# bord_EAGLE_projet_elec_sans_resistance.net
KiCad netlist of a schematic drawn in EAGLE
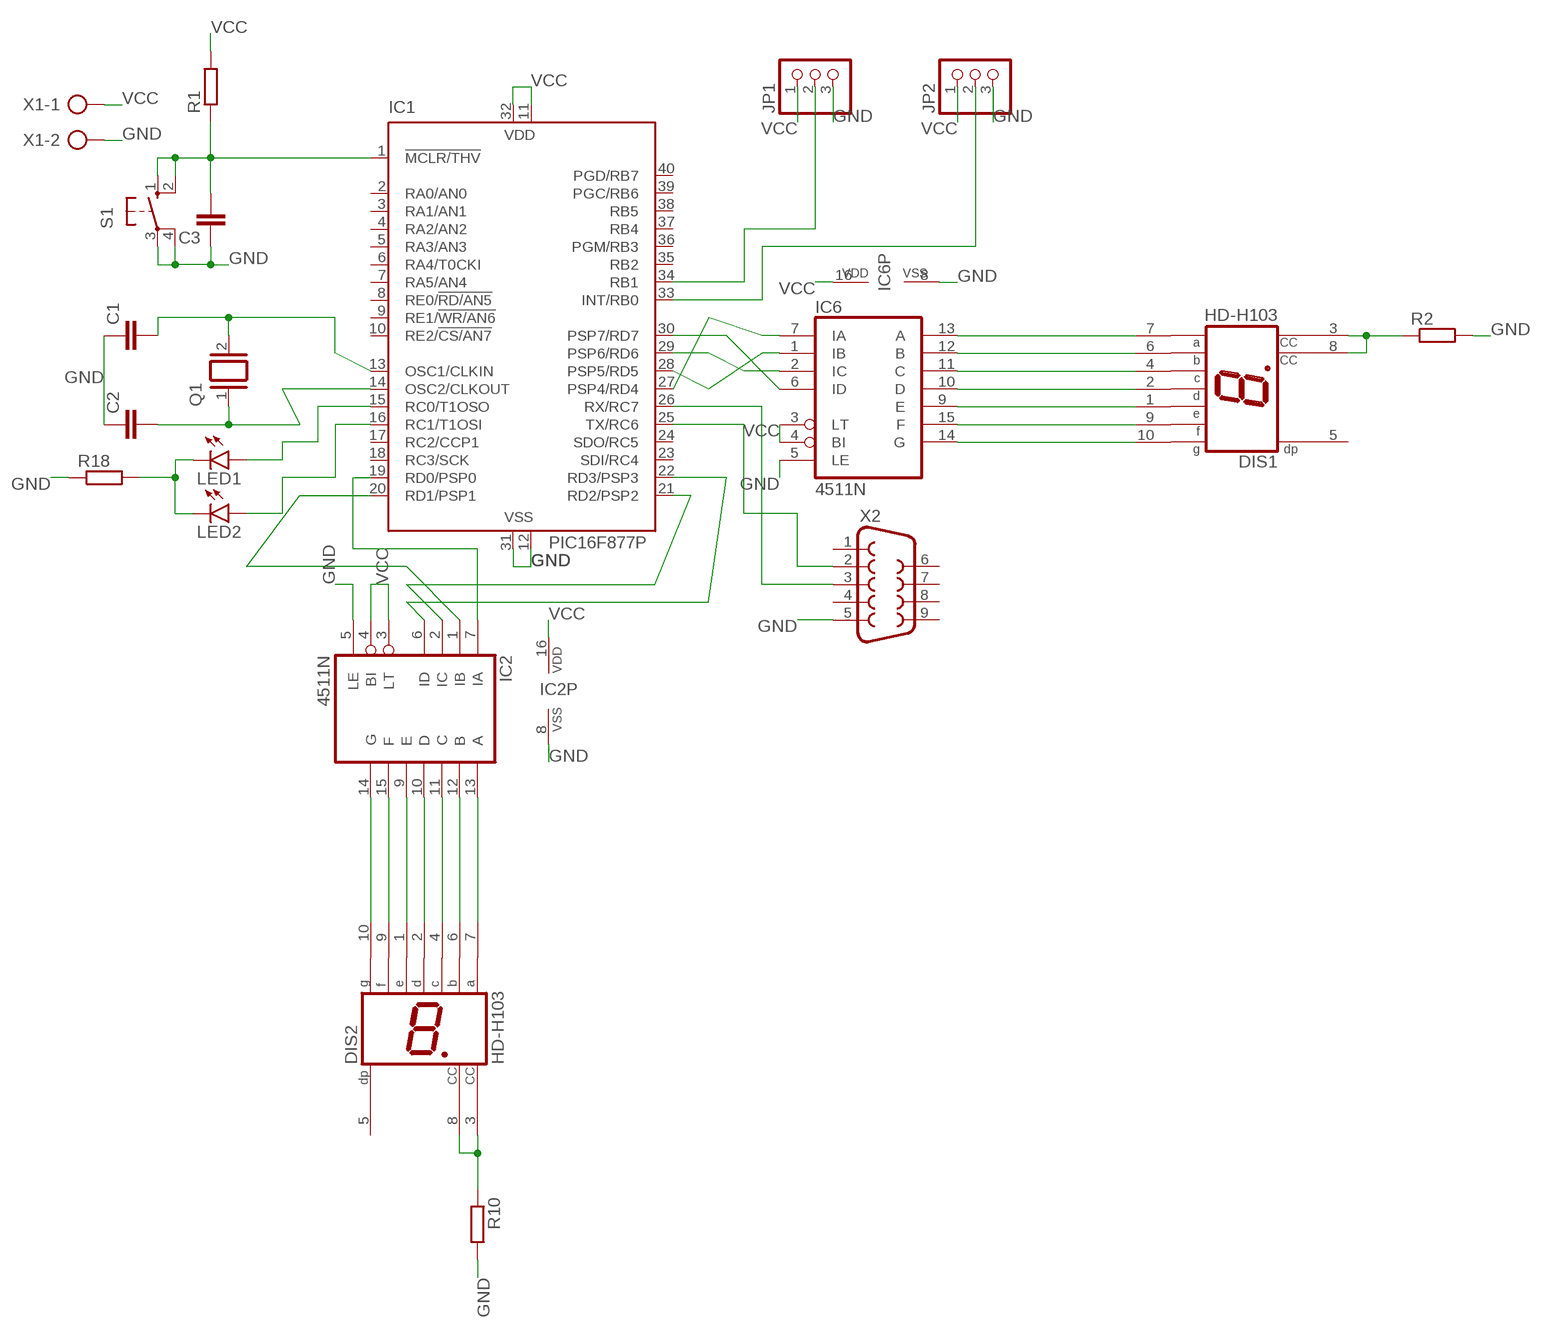
[diagram p0: schematic, sheet 1]

(export (version "E")
  (design (tool "Eeschema 10.0.6"))
  (components
    (comp (ref "C1")
      (value "C-EU025-025X050")
      (footprint "eagle-import:C025-025X050")
      (libsource (lib "eagle-import") (part "C-EU025-025X050"))
    )
    (comp (ref "C2")
      (value "C-EU025-025X050")
      (footprint "eagle-import:C025-025X050")
      (libsource (lib "eagle-import") (part "C-EU025-025X050"))
    )
    (comp (ref "C3")
      (value "C-EU025-024X044")
      (footprint "eagle-import:C025-024X044")
      (libsource (lib "eagle-import") (part "C-EU025-024X044"))
    )
    (comp (ref "DIS1")
      (value "HD-H103")
      (footprint "eagle-import:HDSP-M")
      (libsource (lib "eagle-import") (part "HD-H103"))
    )
    (comp (ref "DIS2")
      (value "HD-H103")
      (footprint "eagle-import:HDSP-M")
      (libsource (lib "eagle-import") (part "HD-H103"))
    )
    (comp (ref "IC1")
      (value "PIC16F877P")
      (footprint "eagle-import:DIL40")
      (fields (field (name "MF") "MICROCHIP") (field (name "MPN") "PIC16F877-04/P"))
      (libsource (lib "eagle-import") (part "PIC16F87P7"))
    )
    (comp (ref "IC2")
      (value "4511N")
      (footprint "eagle-import:DIL16")
      (libsource (lib "eagle-import") (part "4511N"))
    )
    (comp (ref "IC6")
      (value "4511N")
      (footprint "eagle-import:DIL16")
      (libsource (lib "eagle-import") (part "4511N"))
    )
    (comp (ref "JP1")
      (value "PINHD-1X3")
      (footprint "eagle-import:1X03")
      (libsource (lib "eagle-import") (part "PINHD-1X3"))
    )
    (comp (ref "JP2")
      (value "PINHD-1X3")
      (footprint "eagle-import:1X03")
      (libsource (lib "eagle-import") (part "PINHD-1X3"))
    )
    (comp (ref "LED1")
      (value "LED5MM")
      (footprint "eagle-import:LED5MM")
      (libsource (lib "eagle-import") (part "LED5MM"))
    )
    (comp (ref "LED2")
      (value "LED5MM")
      (footprint "eagle-import:LED5MM")
      (libsource (lib "eagle-import") (part "LED5MM"))
    )
    (comp (ref "Q1")
      (value "XTAL/S")
      (footprint "eagle-import:QS")
      (libsource (lib "eagle-import") (part "XTAL/S"))
    )
    (comp (ref "R1")
      (value "R-EU_0204/7")
      (footprint "eagle-import:0204_7")
      (libsource (lib "eagle-import") (part "R-EU_0204/7"))
    )
    (comp (ref "R2")
      (value "R-EU_0204/7")
      (footprint "eagle-import:0204_7")
      (libsource (lib "eagle-import") (part "R-EU_0204/7"))
    )
    (comp (ref "R10")
      (value "R-EU_0204/7")
      (footprint "eagle-import:0204_7")
      (libsource (lib "eagle-import") (part "R-EU_0204/7"))
    )
    (comp (ref "R18")
      (value "R-EU_0204/7")
      (footprint "eagle-import:0204_7")
      (libsource (lib "eagle-import") (part "R-EU_0204/7"))
    )
    (comp (ref "S1")
      (value "10-XX")
      (footprint "eagle-import:B3F-10XX")
      (fields (field (name "MPN") "B3F-1000"))
      (libsource (lib "eagle-import") (part "10-XX"))
    )
    (comp (ref "X1")
      (value "AK300/2")
      (footprint "eagle-import:AK300_2")
      (libsource (lib "eagle-import") (part "AK300/2"))
    )
    (comp (ref "X2")
      (value "F09H")
      (footprint "eagle-import:F09H")
      (libsource (lib "eagle-import") (part "F09H"))
    )
  )
  (nets
    (net (code "1") (name "/GND") (class "Default")
      (node (ref "C1") (pin "1") (pinfunction "1_1") (pintype "passive"))
      (node (ref "C2") (pin "1") (pinfunction "1_1") (pintype "passive"))
      (node (ref "C3") (pin "1") (pinfunction "1_1") (pintype "passive"))
      (node (ref "IC1") (pin "12") (pinfunction "VSS_12") (pintype "power_in"))
      (node (ref "IC1") (pin "31") (pinfunction "VSS_31") (pintype "power_in"))
      (node (ref "IC2") (pin "5") (pinfunction "LE_5") (pintype "input"))
      (node (ref "IC2") (pin "8") (pinfunction "VSS_8") (pintype "power_in"))
      (node (ref "IC6") (pin "5") (pinfunction "LE_5") (pintype "input"))
      (node (ref "IC6") (pin "8") (pinfunction "VSS_8") (pintype "power_in"))
      (node (ref "JP1") (pin "3") (pinfunction "3_3") (pintype "passive"))
      (node (ref "JP2") (pin "3") (pinfunction "3_3") (pintype "passive"))
      (node (ref "R10") (pin "2") (pinfunction "2_2") (pintype "passive"))
      (node (ref "R18") (pin "1") (pinfunction "1_1") (pintype "passive"))
      (node (ref "R2") (pin "2") (pinfunction "2_2") (pintype "passive"))
      (node (ref "S1") (pin "3") (pinfunction "P_3") (pintype "passive"))
      (node (ref "S1") (pin "4") (pinfunction "P1_4") (pintype "passive"))
      (node (ref "X1") (pin "2") (pinfunction "KL_2") (pintype "passive"))
      (node (ref "X2") (pin "5") (pinfunction "5_5") (pintype "passive"))
    )
    (net (code "2") (name "/VCC") (class "Default")
      (node (ref "IC1") (pin "11") (pinfunction "VDD_11") (pintype "power_in"))
      (node (ref "IC1") (pin "32") (pinfunction "VDD_32") (pintype "power_in"))
      (node (ref "IC2") (pin "16") (pinfunction "VDD_16") (pintype "power_in"))
      (node (ref "IC2") (pin "3") (pinfunction "LT_3") (pintype "input"))
      (node (ref "IC2") (pin "4") (pinfunction "BI_4") (pintype "input"))
      (node (ref "IC6") (pin "16") (pinfunction "VDD_16") (pintype "power_in"))
      (node (ref "IC6") (pin "3") (pinfunction "LT_3") (pintype "input"))
      (node (ref "IC6") (pin "4") (pinfunction "BI_4") (pintype "input"))
      (node (ref "JP1") (pin "1") (pinfunction "1_1") (pintype "passive"))
      (node (ref "JP2") (pin "1") (pinfunction "1_1") (pintype "passive"))
      (node (ref "R1") (pin "2") (pinfunction "2_2") (pintype "passive"))
      (node (ref "X1") (pin "1") (pinfunction "KL_1") (pintype "passive"))
    )
    (net (code "3") (name "Net-(DIS1-A)") (class "Default")
      (node (ref "DIS1") (pin "7") (pinfunction "A_7") (pintype "passive"))
      (node (ref "IC6") (pin "13") (pinfunction "A_13") (pintype "output"))
    )
    (net (code "4") (name "Net-(DIS1-B)") (class "Default")
      (node (ref "DIS1") (pin "6") (pinfunction "B_6") (pintype "passive"))
      (node (ref "IC6") (pin "12") (pinfunction "B_12") (pintype "output"))
    )
    (net (code "5") (name "Net-(DIS1-C)") (class "Default")
      (node (ref "DIS1") (pin "4") (pinfunction "C_4") (pintype "passive"))
      (node (ref "IC6") (pin "11") (pinfunction "C_11") (pintype "output"))
    )
    (net (code "6") (name "Net-(DIS1-CC-Pad3)") (class "Default")
      (node (ref "DIS1") (pin "3") (pinfunction "CC_3") (pintype "passive"))
      (node (ref "DIS1") (pin "8") (pinfunction "CC_8") (pintype "passive"))
      (node (ref "R2") (pin "1") (pinfunction "1_1") (pintype "passive"))
    )
    (net (code "7") (name "Net-(DIS1-D)") (class "Default")
      (node (ref "DIS1") (pin "2") (pinfunction "D_2") (pintype "passive"))
      (node (ref "IC6") (pin "10") (pinfunction "D_10") (pintype "output"))
    )
    (net (code "8") (name "Net-(DIS1-E)") (class "Default")
      (node (ref "DIS1") (pin "1") (pinfunction "E_1") (pintype "passive"))
      (node (ref "IC6") (pin "9") (pinfunction "E_9") (pintype "output"))
    )
    (net (code "9") (name "Net-(DIS1-F)") (class "Default")
      (node (ref "DIS1") (pin "9") (pinfunction "F_9") (pintype "passive"))
      (node (ref "IC6") (pin "15") (pinfunction "F_15") (pintype "output"))
    )
    (net (code "10") (name "Net-(DIS1-G)") (class "Default")
      (node (ref "DIS1") (pin "10") (pinfunction "G_10") (pintype "passive"))
      (node (ref "IC6") (pin "14") (pinfunction "G_14") (pintype "output"))
    )
    (net (code "11") (name "Net-(DIS2-A)") (class "Default")
      (node (ref "DIS2") (pin "7") (pinfunction "A_7") (pintype "passive"))
      (node (ref "IC2") (pin "13") (pinfunction "A_13") (pintype "output"))
    )
    (net (code "12") (name "Net-(DIS2-B)") (class "Default")
      (node (ref "DIS2") (pin "6") (pinfunction "B_6") (pintype "passive"))
      (node (ref "IC2") (pin "12") (pinfunction "B_12") (pintype "output"))
    )
    (net (code "13") (name "Net-(DIS2-C)") (class "Default")
      (node (ref "DIS2") (pin "4") (pinfunction "C_4") (pintype "passive"))
      (node (ref "IC2") (pin "11") (pinfunction "C_11") (pintype "output"))
    )
    (net (code "14") (name "Net-(DIS2-CC-Pad3)") (class "Default")
      (node (ref "DIS2") (pin "3") (pinfunction "CC_3") (pintype "passive"))
      (node (ref "DIS2") (pin "8") (pinfunction "CC_8") (pintype "passive"))
      (node (ref "R10") (pin "1") (pinfunction "1_1") (pintype "passive"))
    )
    (net (code "15") (name "Net-(DIS2-D)") (class "Default")
      (node (ref "DIS2") (pin "2") (pinfunction "D_2") (pintype "passive"))
      (node (ref "IC2") (pin "10") (pinfunction "D_10") (pintype "output"))
    )
    (net (code "16") (name "Net-(DIS2-E)") (class "Default")
      (node (ref "DIS2") (pin "1") (pinfunction "E_1") (pintype "passive"))
      (node (ref "IC2") (pin "9") (pinfunction "E_9") (pintype "output"))
    )
    (net (code "17") (name "Net-(DIS2-F)") (class "Default")
      (node (ref "DIS2") (pin "9") (pinfunction "F_9") (pintype "passive"))
      (node (ref "IC2") (pin "15") (pinfunction "F_15") (pintype "output"))
    )
    (net (code "18") (name "Net-(DIS2-G)") (class "Default")
      (node (ref "DIS2") (pin "10") (pinfunction "G_10") (pintype "passive"))
      (node (ref "IC2") (pin "14") (pinfunction "G_14") (pintype "output"))
    )
    (net (code "19") (name "Net-(IC1-INT{slash}RB0)") (class "Default")
      (node (ref "IC1") (pin "33") (pinfunction "INT/RB0_33") (pintype "bidirectional"))
      (node (ref "JP2") (pin "2") (pinfunction "2_2") (pintype "passive"))
    )
    (net (code "20") (name "Net-(IC1-OSC1{slash}CLKIN)") (class "Default")
      (node (ref "C1") (pin "2") (pinfunction "2_2") (pintype "passive"))
      (node (ref "IC1") (pin "13") (pinfunction "OSC1/CLKIN_13") (pintype "input"))
      (node (ref "Q1") (pin "2") (pinfunction "2_2") (pintype "passive"))
    )
    (net (code "21") (name "Net-(IC1-OSC2{slash}CLKOUT)") (class "Default")
      (node (ref "C2") (pin "2") (pinfunction "2_2") (pintype "passive"))
      (node (ref "IC1") (pin "14") (pinfunction "OSC2/CLKOUT_14") (pintype "output"))
      (node (ref "Q1") (pin "1") (pinfunction "1_1") (pintype "passive"))
    )
    (net (code "22") (name "Net-(IC1-PSP4{slash}RD4)") (class "Default")
      (node (ref "IC1") (pin "27") (pinfunction "PSP4/RD4_27") (pintype "bidirectional"))
      (node (ref "IC6") (pin "7") (pinfunction "IA_7") (pintype "input"))
    )
    (net (code "23") (name "Net-(IC1-PSP5{slash}RD5)") (class "Default")
      (node (ref "IC1") (pin "28") (pinfunction "PSP5/RD5_28") (pintype "bidirectional"))
      (node (ref "IC6") (pin "1") (pinfunction "IB_1") (pintype "input"))
    )
    (net (code "24") (name "Net-(IC1-PSP6{slash}RD6)") (class "Default")
      (node (ref "IC1") (pin "29") (pinfunction "PSP6/RD6_29") (pintype "bidirectional"))
      (node (ref "IC6") (pin "2") (pinfunction "IC_2") (pintype "input"))
    )
    (net (code "25") (name "Net-(IC1-PSP7{slash}RD7)") (class "Default")
      (node (ref "IC1") (pin "30") (pinfunction "PSP7/RD7_30") (pintype "bidirectional"))
      (node (ref "IC6") (pin "6") (pinfunction "ID_6") (pintype "input"))
    )
    (net (code "26") (name "Net-(IC1-RB1)") (class "Default")
      (node (ref "IC1") (pin "34") (pinfunction "RB1_34") (pintype "bidirectional"))
      (node (ref "JP1") (pin "2") (pinfunction "2_2") (pintype "passive"))
    )
    (net (code "27") (name "Net-(IC1-RC0{slash}T1OSO)") (class "Default")
      (node (ref "IC1") (pin "15") (pinfunction "RC0/T1OSO_15") (pintype "bidirectional"))
      (node (ref "LED1") (pin "A") (pinfunction "A_A") (pintype "passive"))
    )
    (net (code "28") (name "Net-(IC1-RC1{slash}T1OSI)") (class "Default")
      (node (ref "IC1") (pin "16") (pinfunction "RC1/T1OSI_16") (pintype "bidirectional"))
      (node (ref "LED2") (pin "A") (pinfunction "A_A") (pintype "passive"))
    )
    (net (code "29") (name "Net-(IC1-RD0{slash}PSP0)") (class "Default")
      (node (ref "IC1") (pin "19") (pinfunction "RD0/PSP0_19") (pintype "bidirectional"))
      (node (ref "IC2") (pin "7") (pinfunction "IA_7") (pintype "input"))
    )
    (net (code "30") (name "Net-(IC1-RD1{slash}PSP1)") (class "Default")
      (node (ref "IC1") (pin "20") (pinfunction "RD1/PSP1_20") (pintype "bidirectional"))
      (node (ref "IC2") (pin "1") (pinfunction "IB_1") (pintype "input"))
    )
    (net (code "31") (name "Net-(IC1-RD2{slash}PSP2)") (class "Default")
      (node (ref "IC1") (pin "21") (pinfunction "RD2/PSP2_21") (pintype "bidirectional"))
      (node (ref "IC2") (pin "2") (pinfunction "IC_2") (pintype "input"))
    )
    (net (code "32") (name "Net-(IC1-RD3{slash}PSP3)") (class "Default")
      (node (ref "IC1") (pin "22") (pinfunction "RD3/PSP3_22") (pintype "bidirectional"))
      (node (ref "IC2") (pin "6") (pinfunction "ID_6") (pintype "input"))
    )
    (net (code "33") (name "Net-(IC1-RX{slash}RC7)") (class "Default")
      (node (ref "IC1") (pin "26") (pinfunction "RX/RC7_26") (pintype "bidirectional"))
      (node (ref "X2") (pin "3") (pinfunction "3_3") (pintype "passive"))
    )
    (net (code "34") (name "Net-(IC1-TX{slash}RC6)") (class "Default")
      (node (ref "IC1") (pin "25") (pinfunction "TX/RC6_25") (pintype "bidirectional"))
      (node (ref "X2") (pin "2") (pinfunction "2_2") (pintype "passive"))
    )
    (net (code "35") (name "Net-(IC1-~{MCLR{slash}THV})") (class "Default")
      (node (ref "C3") (pin "2") (pinfunction "2_2") (pintype "passive"))
      (node (ref "IC1") (pin "1") (pinfunction "~{MCLR/THV}_1") (pintype "input"))
      (node (ref "R1") (pin "1") (pinfunction "1_1") (pintype "passive"))
      (node (ref "S1") (pin "1") (pinfunction "S_1") (pintype "passive"))
      (node (ref "S1") (pin "2") (pinfunction "S1_2") (pintype "passive"))
    )
    (net (code "36") (name "Net-(LED1-C)") (class "Default")
      (node (ref "LED1") (pin "K") (pinfunction "C_K") (pintype "passive"))
      (node (ref "LED2") (pin "K") (pinfunction "C_K") (pintype "passive"))
      (node (ref "R18") (pin "2") (pinfunction "2_2") (pintype "passive"))
    )
    (net (code "37") (name "unconnected-(DIS1-DP-Pad5)") (class "Default")
      (node (ref "DIS1") (pin "5") (pinfunction "DP_5") (pintype "passive"))
    )
    (net (code "38") (name "unconnected-(DIS2-DP-Pad5)") (class "Default")
      (node (ref "DIS2") (pin "5") (pinfunction "DP_5") (pintype "passive"))
    )
    (net (code "39") (name "unconnected-(IC1-PGC{slash}RB6-Pad39)") (class "Default")
      (node (ref "IC1") (pin "39") (pinfunction "PGC/RB6_39") (pintype "bidirectional"))
    )
    (net (code "40") (name "unconnected-(IC1-PGD{slash}RB7-Pad40)") (class "Default")
      (node (ref "IC1") (pin "40") (pinfunction "PGD/RB7_40") (pintype "bidirectional"))
    )
    (net (code "41") (name "unconnected-(IC1-PGM{slash}RB3-Pad36)") (class "Default")
      (node (ref "IC1") (pin "36") (pinfunction "PGM/RB3_36") (pintype "bidirectional"))
    )
    (net (code "42") (name "unconnected-(IC1-RA0{slash}AN0-Pad2)") (class "Default")
      (node (ref "IC1") (pin "2") (pinfunction "RA0/AN0_2") (pintype "bidirectional"))
    )
    (net (code "43") (name "unconnected-(IC1-RA1{slash}AN1-Pad3)") (class "Default")
      (node (ref "IC1") (pin "3") (pinfunction "RA1/AN1_3") (pintype "bidirectional"))
    )
    (net (code "44") (name "unconnected-(IC1-RA2{slash}AN2-Pad4)") (class "Default")
      (node (ref "IC1") (pin "4") (pinfunction "RA2/AN2_4") (pintype "bidirectional"))
    )
    (net (code "45") (name "unconnected-(IC1-RA3{slash}AN3-Pad5)") (class "Default")
      (node (ref "IC1") (pin "5") (pinfunction "RA3/AN3_5") (pintype "bidirectional"))
    )
    (net (code "46") (name "unconnected-(IC1-RA4{slash}T0CKI-Pad6)") (class "Default")
      (node (ref "IC1") (pin "6") (pinfunction "RA4/T0CKI_6") (pintype "bidirectional"))
    )
    (net (code "47") (name "unconnected-(IC1-RA5{slash}AN4-Pad7)") (class "Default")
      (node (ref "IC1") (pin "7") (pinfunction "RA5/AN4_7") (pintype "bidirectional"))
    )
    (net (code "48") (name "unconnected-(IC1-RB2-Pad35)") (class "Default")
      (node (ref "IC1") (pin "35") (pinfunction "RB2_35") (pintype "bidirectional"))
    )
    (net (code "49") (name "unconnected-(IC1-RB4-Pad37)") (class "Default")
      (node (ref "IC1") (pin "37") (pinfunction "RB4_37") (pintype "bidirectional"))
    )
    (net (code "50") (name "unconnected-(IC1-RB5-Pad38)") (class "Default")
      (node (ref "IC1") (pin "38") (pinfunction "RB5_38") (pintype "bidirectional"))
    )
    (net (code "51") (name "unconnected-(IC1-RC2{slash}CCP1-Pad17)") (class "Default")
      (node (ref "IC1") (pin "17") (pinfunction "RC2/CCP1_17") (pintype "bidirectional"))
    )
    (net (code "52") (name "unconnected-(IC1-RC3{slash}SCK-Pad18)") (class "Default")
      (node (ref "IC1") (pin "18") (pinfunction "RC3/SCK_18") (pintype "bidirectional"))
    )
    (net (code "53") (name "unconnected-(IC1-RE0{slash}~{RD{slash}AN5}-Pad8)") (class "Default")
      (node (ref "IC1") (pin "8") (pinfunction "RE0/~{RD/AN5}_8") (pintype "bidirectional"))
    )
    (net (code "54") (name "unconnected-(IC1-RE1{slash}~{WR{slash}AN6}-Pad9)") (class "Default")
      (node (ref "IC1") (pin "9") (pinfunction "RE1/~{WR/AN6}_9") (pintype "bidirectional"))
    )
    (net (code "55") (name "unconnected-(IC1-RE2{slash}~{CS{slash}AN7}-Pad10)") (class "Default")
      (node (ref "IC1") (pin "10") (pinfunction "RE2/~{CS/AN7}_10") (pintype "bidirectional"))
    )
    (net (code "56") (name "unconnected-(IC1-SDI{slash}RC4-Pad23)") (class "Default")
      (node (ref "IC1") (pin "23") (pinfunction "SDI/RC4_23") (pintype "bidirectional"))
    )
    (net (code "57") (name "unconnected-(IC1-SDO{slash}RC5-Pad24)") (class "Default")
      (node (ref "IC1") (pin "24") (pinfunction "SDO/RC5_24") (pintype "bidirectional"))
    )
    (net (code "58") (name "unconnected-(X2-Pad1)") (class "Default")
      (node (ref "X2") (pin "1") (pinfunction "1_1") (pintype "passive"))
    )
    (net (code "59") (name "unconnected-(X2-Pad4)") (class "Default")
      (node (ref "X2") (pin "4") (pinfunction "4_4") (pintype "passive"))
    )
    (net (code "60") (name "unconnected-(X2-Pad6)") (class "Default")
      (node (ref "X2") (pin "6") (pinfunction "6_6") (pintype "passive"))
    )
    (net (code "61") (name "unconnected-(X2-Pad7)") (class "Default")
      (node (ref "X2") (pin "7") (pinfunction "7_7") (pintype "passive"))
    )
    (net (code "62") (name "unconnected-(X2-Pad8)") (class "Default")
      (node (ref "X2") (pin "8") (pinfunction "8_8") (pintype "passive"))
    )
    (net (code "63") (name "unconnected-(X2-Pad9)") (class "Default")
      (node (ref "X2") (pin "9") (pinfunction "9_9") (pintype "passive"))
    )
  )
)
